# ATtiny_4585_dev_board_with_power_reg.net
KiCad netlist of a schematic drawn in EAGLE
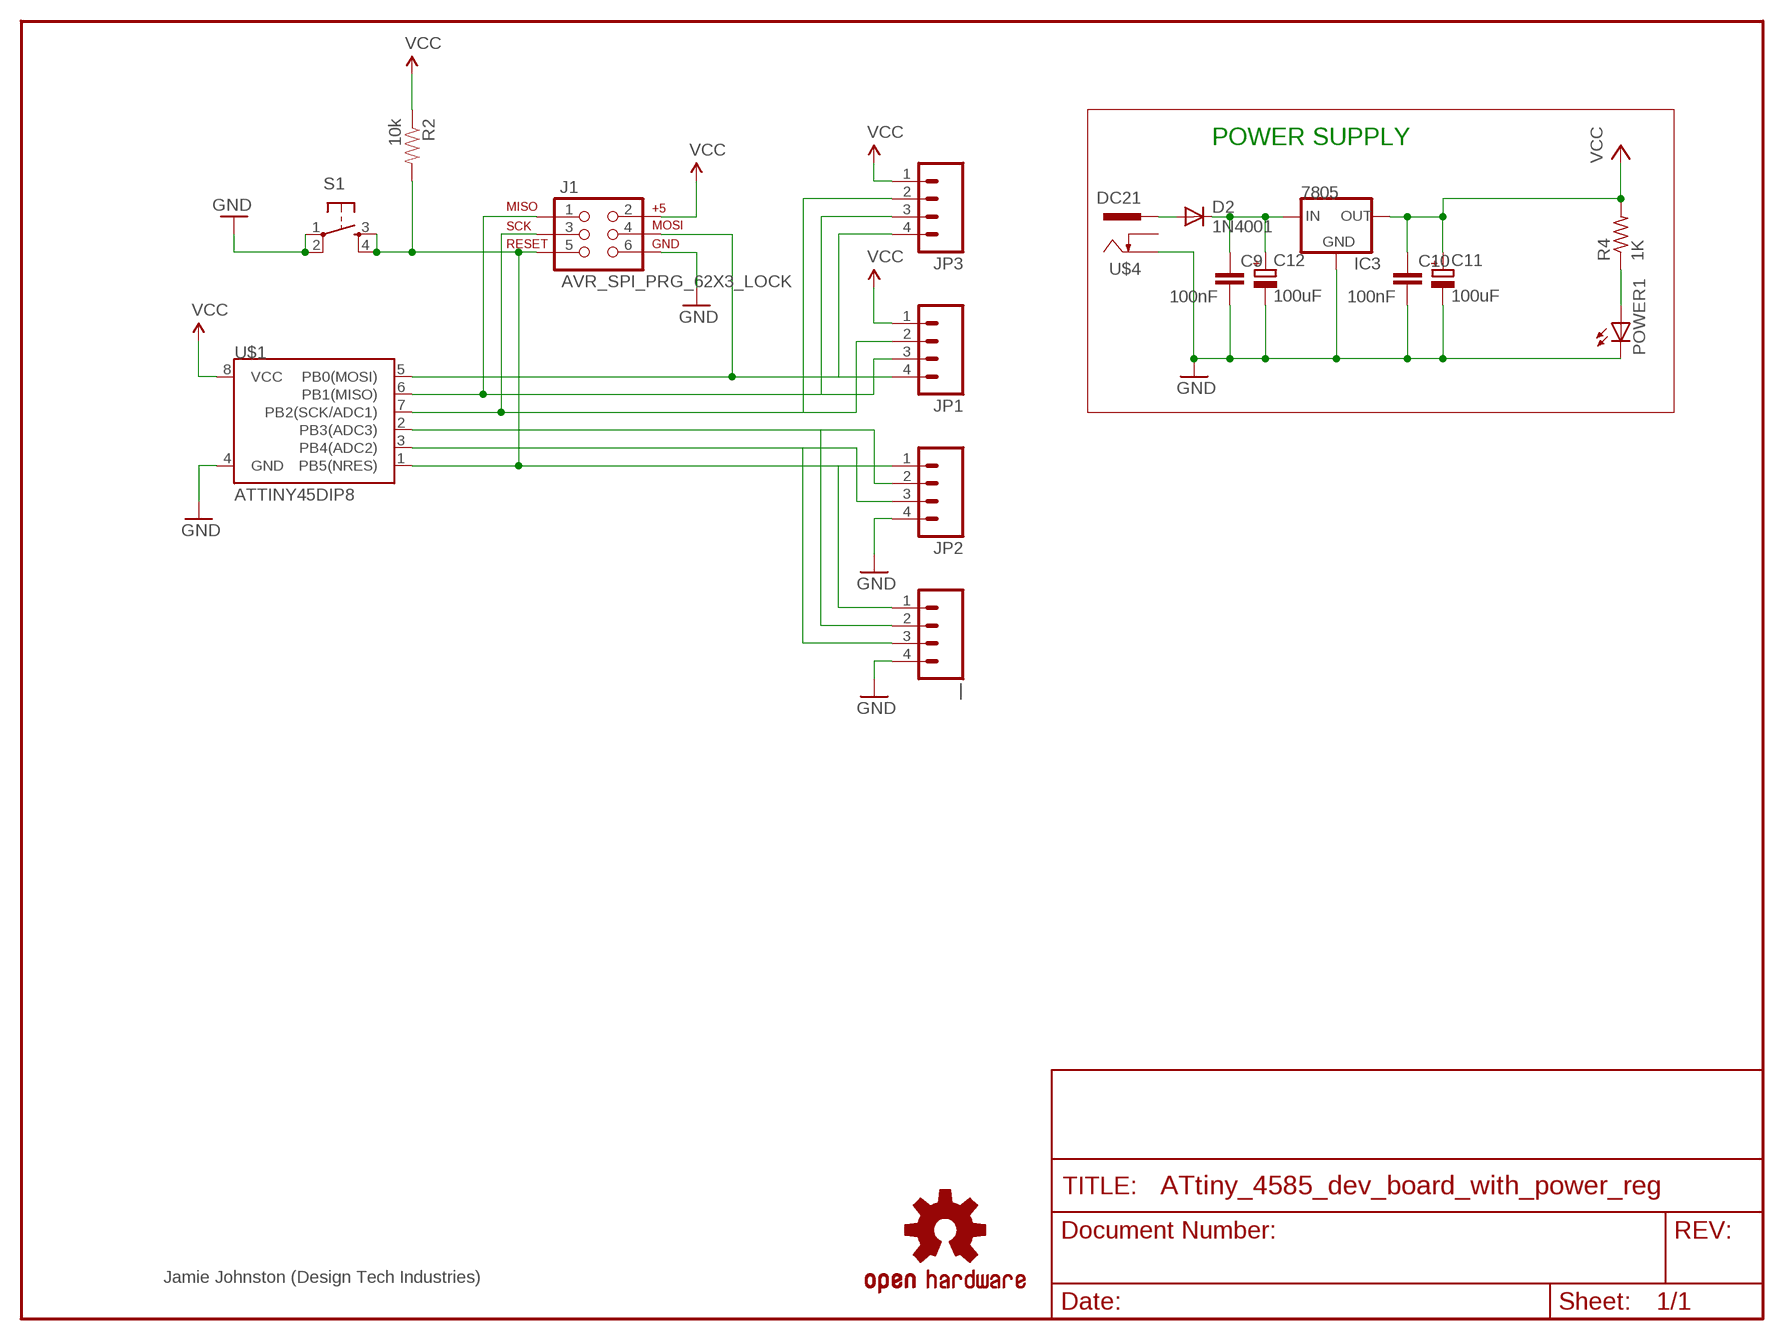
[diagram p0: schematic, sheet 1]

(export (version "E")
  (design (tool "Eeschema 10.0.6"))
  (components
    (comp (ref "C9")
      (value "100nF")
      (footprint "eagle-import:C050-030X075")
      (libsource (lib "eagle-import") (part "C-EU050-030X075"))
    )
    (comp (ref "C10")
      (value "100nF")
      (footprint "eagle-import:C050-030X075")
      (libsource (lib "eagle-import") (part "C-EU050-030X075"))
    )
    (comp (ref "C11")
      (value "100uF")
      (footprint "eagle-import:E2,5-6")
      (libsource (lib "eagle-import") (part "CPOL-EUE2.5-6"))
    )
    (comp (ref "C12")
      (value "100uF")
      (footprint "eagle-import:E2,5-6")
      (libsource (lib "eagle-import") (part "CPOL-EUE2.5-6"))
    )
    (comp (ref "D2")
      (value "1N4001")
      (footprint "eagle-import:DO41-10")
      (libsource (lib "eagle-import") (part "1N4004"))
    )
    (comp (ref "IC3")
      (value "7805")
      (footprint "eagle-import:TO220-IGO")
      (libsource (lib "eagle-import") (part "V_REG_78XXSINK"))
    )
    (comp (ref "J1")
      (value "AVR_SPI_PRG_62X3_LOCK")
      (footprint "eagle-import:2X3_LOCK")
      (libsource (lib "eagle-import") (part "AVR_SPI_PRG_62X3_LOCK"))
    )
    (comp (ref "JP1")
      (value "M04LOCK")
      (footprint "eagle-import:1X04_LOCK")
      (libsource (lib "eagle-import") (part "M04LOCK"))
    )
    (comp (ref "JP2")
      (value "M04LOCK")
      (footprint "eagle-import:1X04_LOCK")
      (libsource (lib "eagle-import") (part "M04LOCK"))
    )
    (comp (ref "JP3")
      (value "M04LOCK")
      (footprint "eagle-import:1X04_LOCK")
      (libsource (lib "eagle-import") (part "M04LOCK"))
    )
    (comp (ref "POWER1")
      (value "LED3MM")
      (footprint "eagle-import:LED3MM")
      (libsource (lib "eagle-import") (part "LED3MM"))
    )
    (comp (ref "R2")
      (value "10k")
      (footprint "eagle-import:AXIAL-0.4")
      (libsource (lib "eagle-import") (part "RESISTORPTH-1/4W"))
    )
    (comp (ref "R4")
      (value "1K")
      (footprint "eagle-import:0207_2V")
      (libsource (lib "eagle-import") (part "R-US_0207/2V"))
    )
    (comp (ref "S1")
      (value "TAC_SWITCHPTH")
      (footprint "eagle-import:TACTILE-PTH")
      (libsource (lib "eagle-import") (part "TAC_SWITCHPTH"))
    )
    (comp (ref "U$1")
      (value "ATTINY45DIP8")
      (footprint "eagle-import:DIP08")
      (libsource (lib "eagle-import") (part "ATTINY45DIP8"))
    )
    (comp (ref "U$3")
      (value "OSHW-LOGOM")
      (footprint "eagle-import:OSHW-LOGO-M")
      (libsource (lib "eagle-import") (part "OSHW-LOGOM"))
    )
    (comp (ref "U$4")
      (value "DC21")
      (footprint "eagle-import:DCSKT")
      (libsource (lib "eagle-import") (part "DC21"))
    )
    (comp (ref "|")
      (value "M04LOCK")
      (footprint "eagle-import:1X04_LOCK")
      (libsource (lib "eagle-import") (part "M04LOCK"))
    )
  )
  (nets
    (net (code "1") (name "GND") (class "Default")
      (node (ref "C10") (pin "2") (pinfunction "2_2") (pintype "passive"))
      (node (ref "C11") (pin "-") (pinfunction "-_-") (pintype "passive"))
      (node (ref "C12") (pin "-") (pinfunction "-_-") (pintype "passive"))
      (node (ref "C9") (pin "2") (pinfunction "2_2") (pintype "passive"))
      (node (ref "IC3") (pin "GND") (pinfunction "GND_GND") (pintype "input"))
      (node (ref "J1") (pin "6") (pinfunction "6_6") (pintype "passive"))
      (node (ref "JP2") (pin "4") (pinfunction "4_4") (pintype "passive"))
      (node (ref "POWER1") (pin "K") (pinfunction "C_K") (pintype "passive"))
      (node (ref "S1") (pin "1") (pinfunction "1_1") (pintype "passive"))
      (node (ref "S1") (pin "2") (pinfunction "2_2") (pintype "passive"))
      (node (ref "U$1") (pin "4") (pinfunction "GND_4") (pintype "bidirectional"))
      (node (ref "U$4") (pin "2") (pinfunction "2_2") (pintype "passive"))
      (node (ref "|") (pin "4") (pinfunction "4_4") (pintype "passive"))
    )
    (net (code "2") (name "Net-(C12-Pad+)") (class "Default")
      (node (ref "C12") (pin "+") (pinfunction "+_+") (pintype "passive"))
      (node (ref "C9") (pin "1") (pinfunction "1_1") (pintype "passive"))
      (node (ref "D2") (pin "C") (pinfunction "C_C") (pintype "passive"))
      (node (ref "IC3") (pin "IN") (pinfunction "IN_IN") (pintype "input"))
    )
    (net (code "3") (name "Net-(D2-PadA)") (class "Default")
      (node (ref "D2") (pin "A") (pinfunction "A_A") (pintype "passive"))
      (node (ref "U$4") (pin "1") (pinfunction "1_1") (pintype "passive"))
    )
    (net (code "4") (name "Net-(POWER1-PadA)") (class "Default")
      (node (ref "POWER1") (pin "A") (pinfunction "A_A") (pintype "passive"))
      (node (ref "R4") (pin "1") (pinfunction "1_1") (pintype "passive"))
    )
    (net (code "5") (name "Net-(R2-2)") (class "Default")
      (node (ref "J1") (pin "5") (pinfunction "5_5") (pintype "passive"))
      (node (ref "JP2") (pin "1") (pinfunction "1_1") (pintype "passive"))
      (node (ref "R2") (pin "P$2") (pinfunction "2_P$2") (pintype "passive"))
      (node (ref "S1") (pin "3") (pinfunction "3_3") (pintype "passive"))
      (node (ref "S1") (pin "4") (pinfunction "4_4") (pintype "passive"))
      (node (ref "U$1") (pin "1") (pinfunction "PB5(NRES)_1") (pintype "bidirectional"))
      (node (ref "|") (pin "1") (pinfunction "1_1") (pintype "passive"))
    )
    (net (code "6") (name "Net-(U$1-PB0(MOSI))") (class "Default")
      (node (ref "J1") (pin "4") (pinfunction "4_4") (pintype "passive"))
      (node (ref "JP1") (pin "4") (pinfunction "4_4") (pintype "passive"))
      (node (ref "JP3") (pin "4") (pinfunction "4_4") (pintype "passive"))
      (node (ref "U$1") (pin "5") (pinfunction "PB0(MOSI)_5") (pintype "bidirectional"))
    )
    (net (code "7") (name "Net-(U$1-PB1(MISO))") (class "Default")
      (node (ref "J1") (pin "1") (pinfunction "1_1") (pintype "passive"))
      (node (ref "JP1") (pin "3") (pinfunction "3_3") (pintype "passive"))
      (node (ref "JP3") (pin "3") (pinfunction "3_3") (pintype "passive"))
      (node (ref "U$1") (pin "6") (pinfunction "PB1(MISO)_6") (pintype "bidirectional"))
    )
    (net (code "8") (name "Net-(U$1-PB2(SCK{slash}ADC1))") (class "Default")
      (node (ref "J1") (pin "3") (pinfunction "3_3") (pintype "passive"))
      (node (ref "JP1") (pin "2") (pinfunction "2_2") (pintype "passive"))
      (node (ref "JP3") (pin "2") (pinfunction "2_2") (pintype "passive"))
      (node (ref "U$1") (pin "7") (pinfunction "PB2(SCK/ADC1)_7") (pintype "bidirectional"))
    )
    (net (code "9") (name "Net-(U$1-PB3(ADC3))") (class "Default")
      (node (ref "JP2") (pin "2") (pinfunction "2_2") (pintype "passive"))
      (node (ref "U$1") (pin "2") (pinfunction "PB3(ADC3)_2") (pintype "bidirectional"))
      (node (ref "|") (pin "2") (pinfunction "2_2") (pintype "passive"))
    )
    (net (code "10") (name "Net-(U$1-PB4(ADC2))") (class "Default")
      (node (ref "JP2") (pin "3") (pinfunction "3_3") (pintype "passive"))
      (node (ref "U$1") (pin "3") (pinfunction "PB4(ADC2)_3") (pintype "bidirectional"))
      (node (ref "|") (pin "3") (pinfunction "3_3") (pintype "passive"))
    )
    (net (code "11") (name "VCC") (class "Default")
      (node (ref "C10") (pin "1") (pinfunction "1_1") (pintype "passive"))
      (node (ref "C11") (pin "+") (pinfunction "+_+") (pintype "passive"))
      (node (ref "IC3") (pin "OUT") (pinfunction "OUT_OUT") (pintype "output"))
      (node (ref "J1") (pin "2") (pinfunction "2_2") (pintype "passive"))
      (node (ref "JP1") (pin "1") (pinfunction "1_1") (pintype "passive"))
      (node (ref "JP3") (pin "1") (pinfunction "1_1") (pintype "passive"))
      (node (ref "R2") (pin "P$1") (pinfunction "1_P$1") (pintype "passive"))
      (node (ref "R4") (pin "2") (pinfunction "2_2") (pintype "passive"))
      (node (ref "U$1") (pin "8") (pinfunction "VCC_8") (pintype "bidirectional"))
    )
    (net (code "12") (name "unconnected-(U$4-Pad3)") (class "Default")
      (node (ref "U$4") (pin "3") (pinfunction "3_3") (pintype "passive"))
    )
  )
)
